# ai.net
KiCad netlist of a schematic drawn in Altium Designer
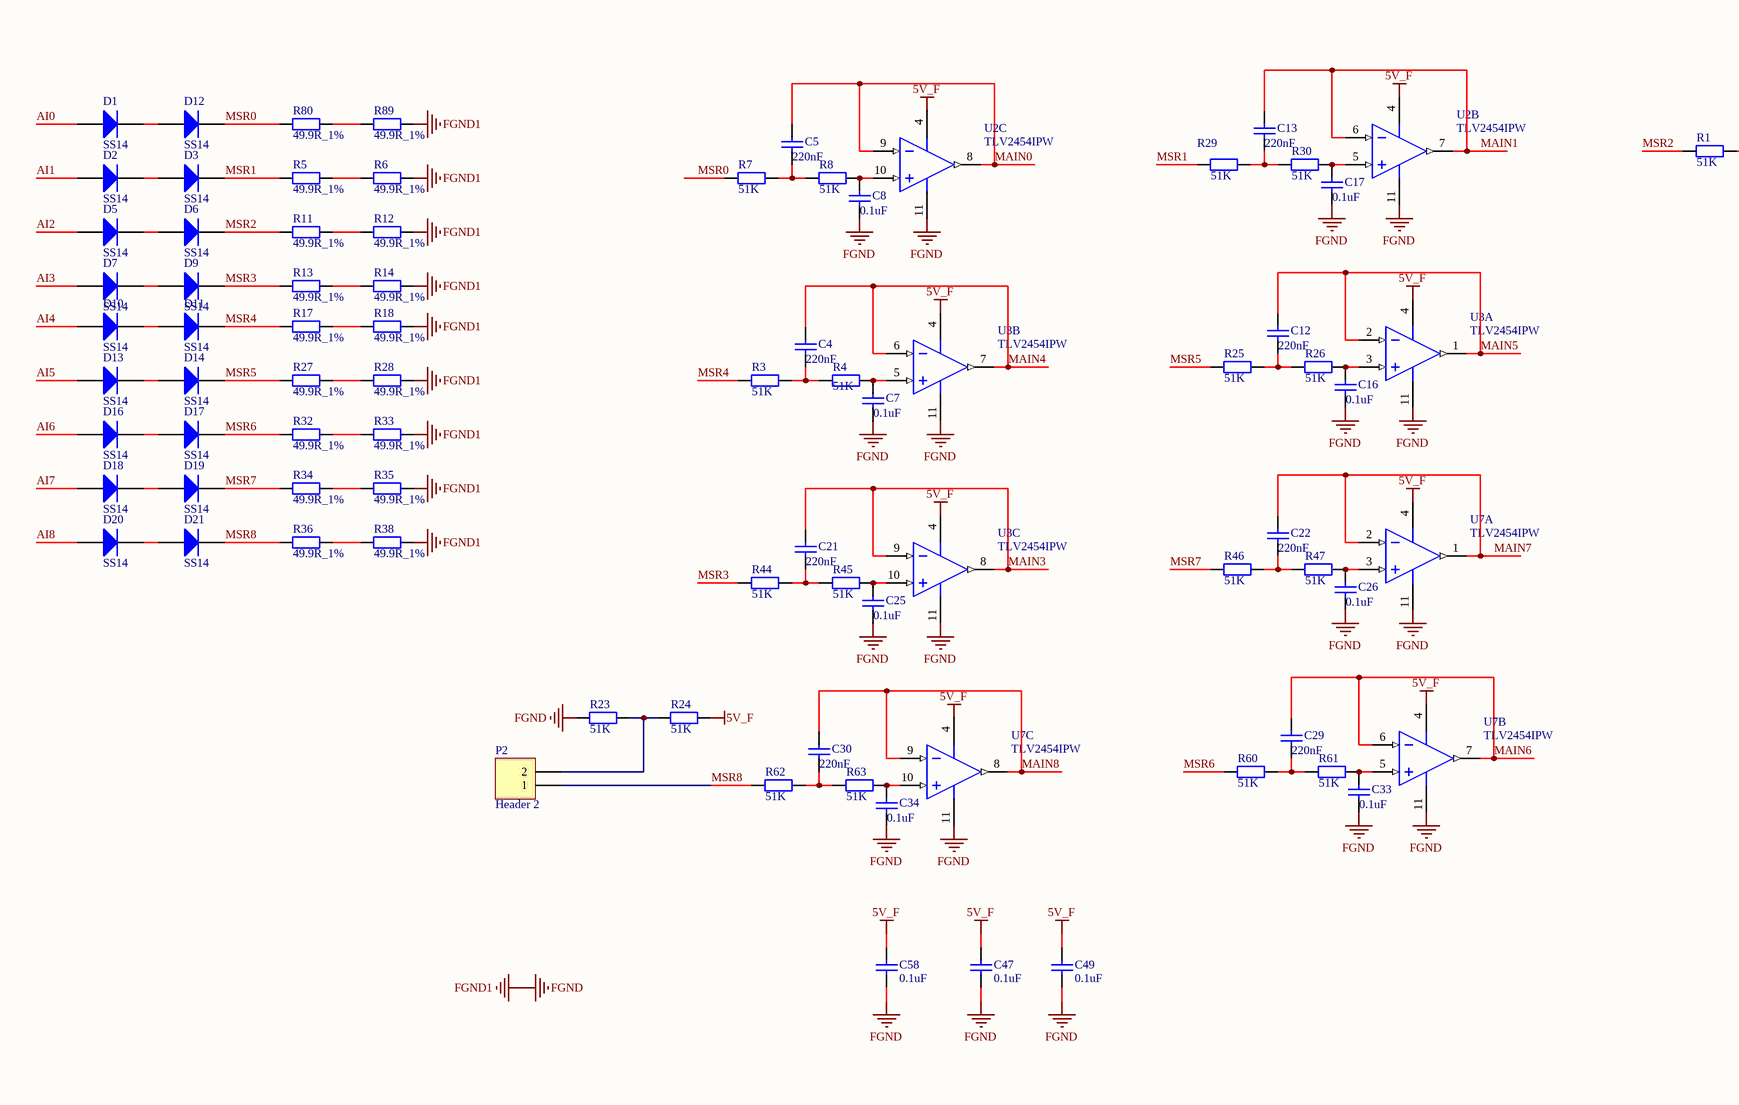
[diagram p0: ai.SchDoc, top left]
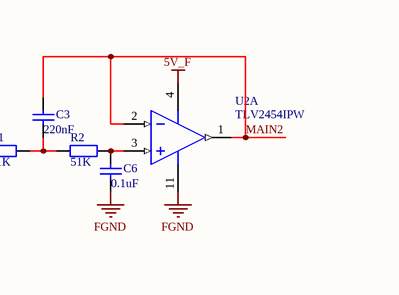
[diagram p1: ai.SchDoc, top right]
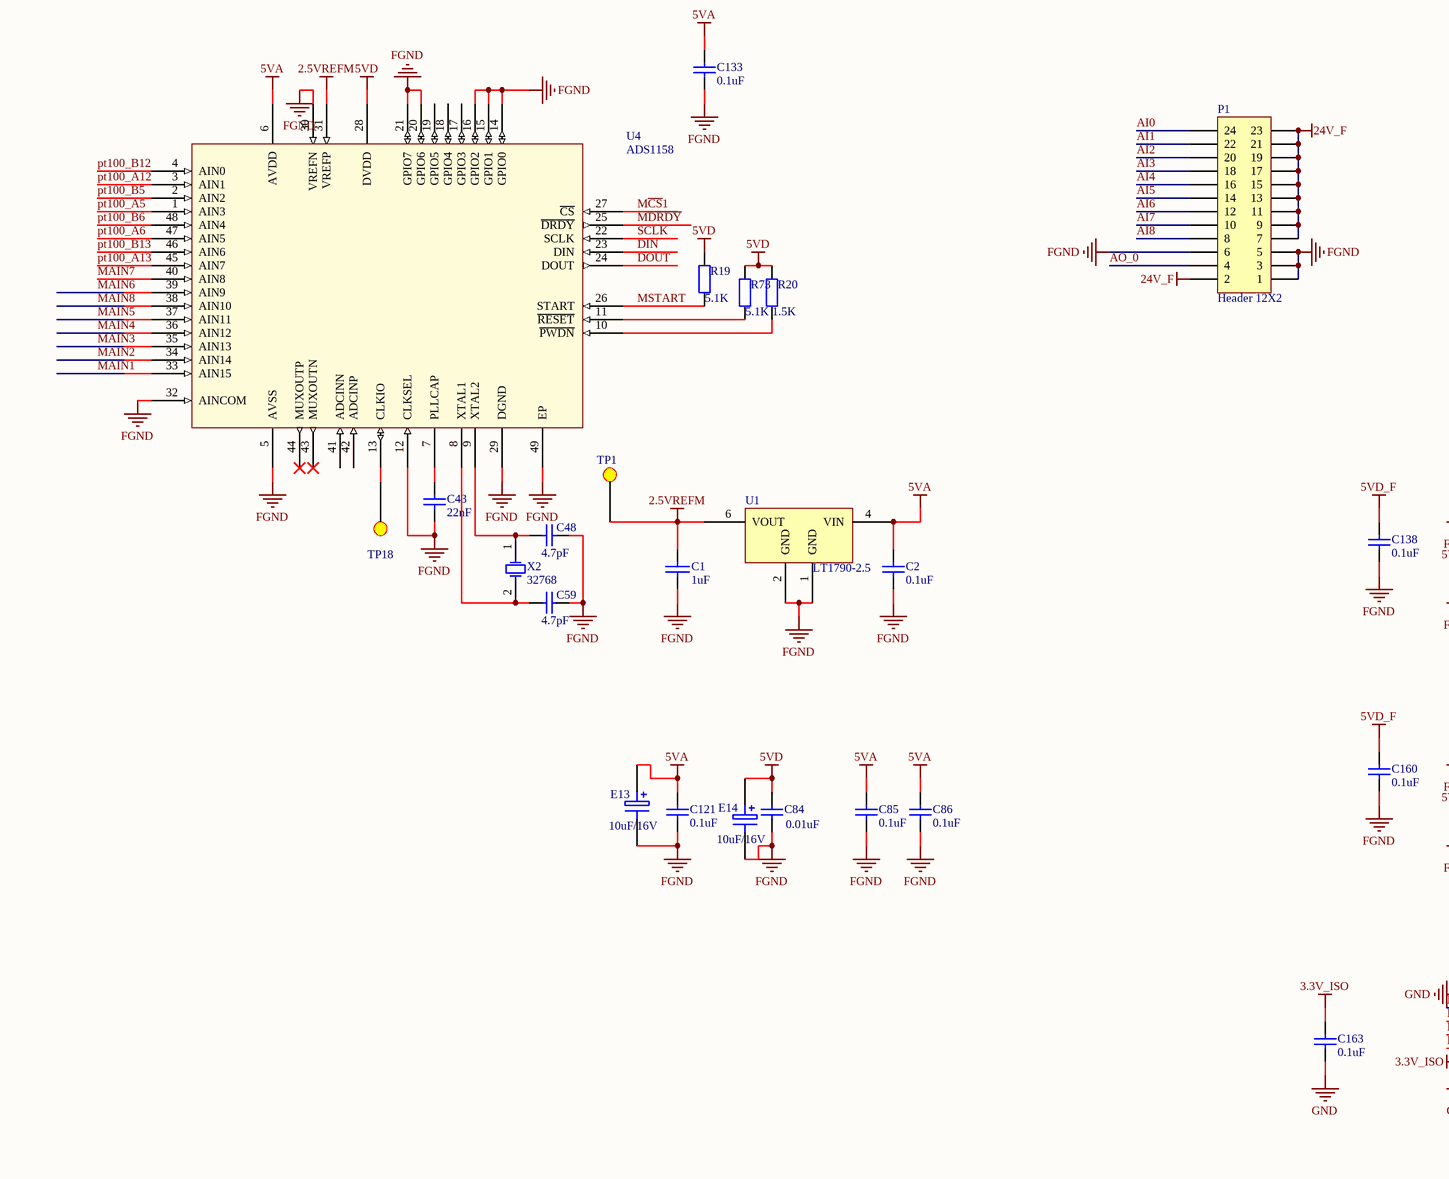
[diagram p2: ai.SchDoc, bottom left]
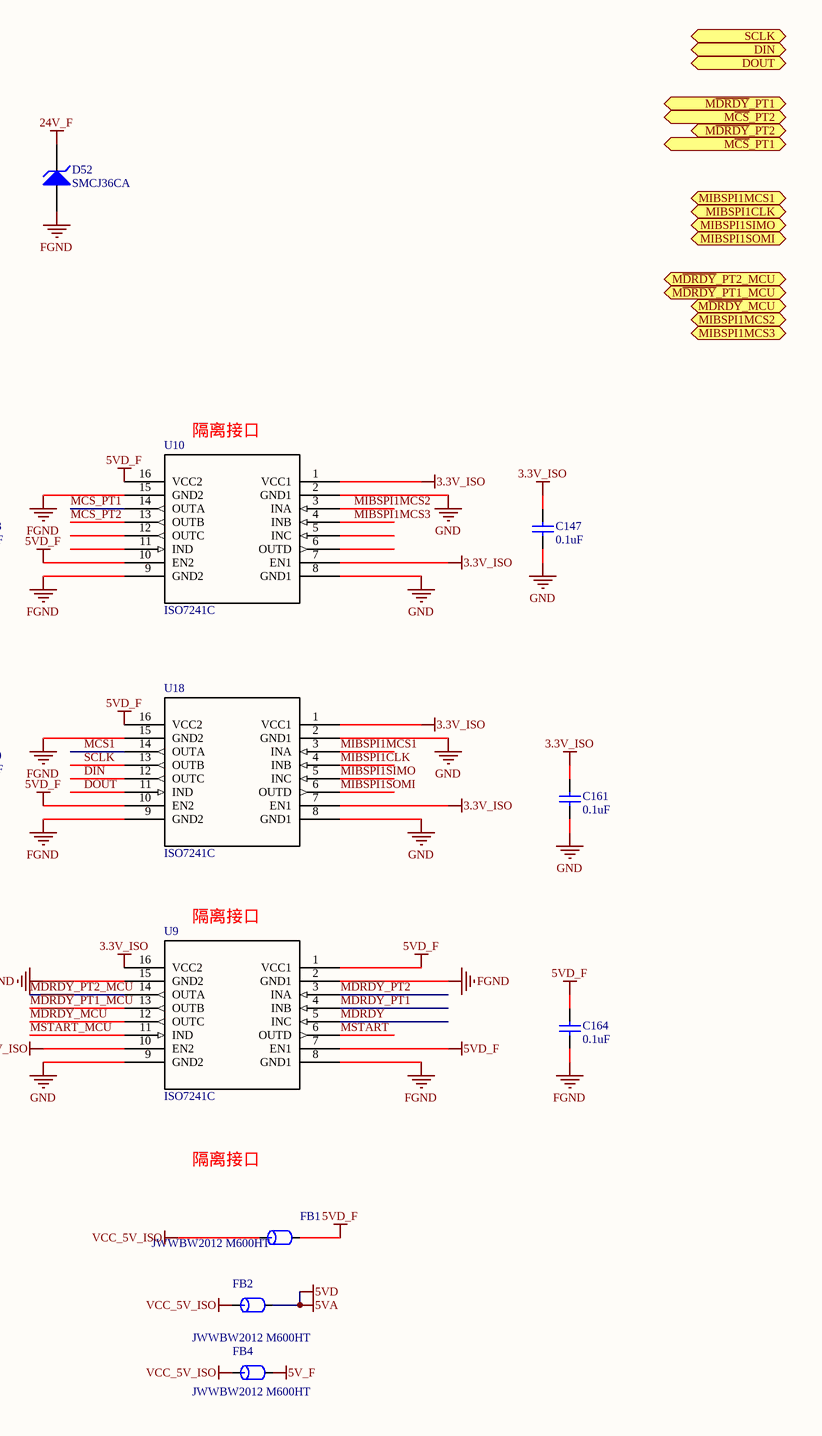
[diagram p3: ai.SchDoc, bottom right]

(export (version "E")
  (design (tool "Eeschema 10.0.6"))
  (components
    (comp (ref "C1")
      (value "1uF")
      (footprint "0603C")
      (description "Capacitor")
      (libsource (lib "*") (part "CAP"))
    )
    (comp (ref "C2")
      (value "0.1uF")
      (footprint "0603C")
      (description "Capacitor")
      (libsource (lib "Miscellaneous Devices") (part "Cap"))
    )
    (comp (ref "C3")
      (value "220nF")
      (footprint "0805C")
      (description "Capacitor")
      (libsource (lib "Miscellaneous Devices") (part "Cap"))
    )
    (comp (ref "C4")
      (value "220nF")
      (footprint "0805C")
      (description "Capacitor")
      (libsource (lib "Miscellaneous Devices") (part "Cap"))
    )
    (comp (ref "C5")
      (value "220nF")
      (footprint "0805C")
      (description "Capacitor")
      (libsource (lib "Miscellaneous Devices") (part "Cap"))
    )
    (comp (ref "C6")
      (value "0.1uF")
      (footprint "0603C")
      (description "Capacitor")
      (libsource (lib "Miscellaneous Devices") (part "Cap"))
    )
    (comp (ref "C7")
      (value "0.1uF")
      (footprint "0603C")
      (description "Capacitor")
      (libsource (lib "Miscellaneous Devices") (part "Cap"))
    )
    (comp (ref "C8")
      (value "0.1uF")
      (footprint "0603C")
      (description "Capacitor")
      (libsource (lib "Miscellaneous Devices") (part "Cap"))
    )
    (comp (ref "C12")
      (value "220nF")
      (footprint "0805C")
      (description "Capacitor")
      (libsource (lib "Miscellaneous Devices") (part "Cap"))
    )
    (comp (ref "C13")
      (value "220nF")
      (footprint "0805C")
      (description "Capacitor")
      (libsource (lib "Miscellaneous Devices") (part "Cap"))
    )
    (comp (ref "C16")
      (value "0.1uF")
      (footprint "0603C")
      (description "Capacitor")
      (libsource (lib "Miscellaneous Devices") (part "Cap"))
    )
    (comp (ref "C17")
      (value "0.1uF")
      (footprint "0603C")
      (description "Capacitor")
      (libsource (lib "Miscellaneous Devices") (part "Cap"))
    )
    (comp (ref "C21")
      (value "220nF")
      (footprint "0805C")
      (description "Capacitor")
      (libsource (lib "Miscellaneous Devices") (part "Cap"))
    )
    (comp (ref "C22")
      (value "220nF")
      (footprint "0805C")
      (description "Capacitor")
      (libsource (lib "Miscellaneous Devices") (part "Cap"))
    )
    (comp (ref "C25")
      (value "0.1uF")
      (footprint "0603C")
      (description "Capacitor")
      (libsource (lib "Miscellaneous Devices") (part "Cap"))
    )
    (comp (ref "C26")
      (value "0.1uF")
      (footprint "0603C")
      (description "Capacitor")
      (libsource (lib "Miscellaneous Devices") (part "Cap"))
    )
    (comp (ref "C29")
      (value "220nF")
      (footprint "0805C")
      (description "Capacitor")
      (libsource (lib "Miscellaneous Devices") (part "Cap"))
    )
    (comp (ref "C30")
      (value "220nF")
      (footprint "0805C")
      (description "Capacitor")
      (libsource (lib "Miscellaneous Devices") (part "Cap"))
    )
    (comp (ref "C33")
      (value "0.1uF")
      (footprint "0603C")
      (description "Capacitor")
      (libsource (lib "Miscellaneous Devices") (part "Cap"))
    )
    (comp (ref "C34")
      (value "0.1uF")
      (footprint "0603C")
      (description "Capacitor")
      (libsource (lib "Miscellaneous Devices") (part "Cap"))
    )
    (comp (ref "C43")
      (value "22nF")
      (footprint "0805C")
      (description "Capacitor")
      (libsource (lib "Miscellaneous Devices") (part "Cap"))
    )
    (comp (ref "C47")
      (value "0.1uF")
      (footprint "0603C")
      (description "Capacitor")
      (libsource (lib "Miscellaneous Devices") (part "Cap"))
    )
    (comp (ref "C48")
      (value "4.7pF")
      (footprint "0603C")
      (description "Capacitor")
      (libsource (lib "Miscellaneous Devices") (part "Cap"))
    )
    (comp (ref "C49")
      (value "0.1uF")
      (footprint "0603C")
      (description "Capacitor")
      (libsource (lib "Miscellaneous Devices") (part "Cap"))
    )
    (comp (ref "C58")
      (value "0.1uF")
      (footprint "0603C")
      (description "Capacitor")
      (libsource (lib "Miscellaneous Devices") (part "Cap"))
    )
    (comp (ref "C59")
      (value "4.7pF")
      (footprint "0603C")
      (description "Capacitor")
      (libsource (lib "Miscellaneous Devices") (part "Cap"))
    )
    (comp (ref "C84")
      (value "0.01uF")
      (footprint "0603C")
      (description "Capacitor")
      (libsource (lib "Miscellaneous Devices") (part "Cap"))
    )
    (comp (ref "C85")
      (value "0.1uF")
      (footprint "0603C")
      (description "Capacitor")
      (libsource (lib "Miscellaneous Devices") (part "Cap"))
    )
    (comp (ref "C86")
      (value "0.1uF")
      (footprint "0603C")
      (description "Capacitor")
      (libsource (lib "Miscellaneous Devices") (part "Cap"))
    )
    (comp (ref "C121")
      (value "0.1uF")
      (footprint "0603C")
      (description "Capacitor")
      (libsource (lib "Miscellaneous Devices") (part "Cap"))
    )
    (comp (ref "C133")
      (value "0.1uF")
      (footprint "0603C")
      (description "Capacitor")
      (libsource (lib "Miscellaneous Devices") (part "Cap"))
    )
    (comp (ref "C138")
      (value "0.1uF")
      (footprint "0603C")
      (description "Capacitor")
      (libsource (lib "Miscellaneous Devices") (part "Cap"))
    )
    (comp (ref "C147")
      (value "0.1uF")
      (footprint "0603C")
      (description "Capacitor")
      (libsource (lib "Miscellaneous Devices") (part "Cap"))
    )
    (comp (ref "C160")
      (value "0.1uF")
      (footprint "0603C")
      (description "Capacitor")
      (libsource (lib "Miscellaneous Devices") (part "Cap"))
    )
    (comp (ref "C161")
      (value "0.1uF")
      (footprint "0603C")
      (description "Capacitor")
      (libsource (lib "Miscellaneous Devices") (part "Cap"))
    )
    (comp (ref "C163")
      (value "0.1uF")
      (footprint "0603C")
      (description "Capacitor")
      (libsource (lib "Miscellaneous Devices") (part "Cap"))
    )
    (comp (ref "C164")
      (value "0.1uF")
      (footprint "0603C")
      (description "Capacitor")
      (libsource (lib "Miscellaneous Devices") (part "Cap"))
    )
    (comp (ref "D1")
      (value "SS14")
      (footprint "DO-214AC")
      (description "Default Diode")
      (libsource (lib "Miscellaneous Devices") (part "Diode"))
    )
    (comp (ref "D2")
      (value "SS14")
      (footprint "DO-214AC")
      (description "Default Diode")
      (libsource (lib "Miscellaneous Devices") (part "Diode"))
    )
    (comp (ref "D3")
      (value "SS14")
      (footprint "DO-214AC")
      (description "Default Diode")
      (libsource (lib "Miscellaneous Devices") (part "Diode"))
    )
    (comp (ref "D5")
      (value "SS14")
      (footprint "DO-214AC")
      (description "Default Diode")
      (libsource (lib "Miscellaneous Devices") (part "Diode"))
    )
    (comp (ref "D6")
      (value "SS14")
      (footprint "DO-214AC")
      (description "Default Diode")
      (libsource (lib "Miscellaneous Devices") (part "Diode"))
    )
    (comp (ref "D7")
      (value "SS14")
      (footprint "DO-214AC")
      (description "Default Diode")
      (libsource (lib "Miscellaneous Devices") (part "Diode"))
    )
    (comp (ref "D9")
      (value "SS14")
      (footprint "DO-214AC")
      (description "Default Diode")
      (libsource (lib "Miscellaneous Devices") (part "Diode"))
    )
    (comp (ref "D10")
      (value "SS14")
      (footprint "DO-214AC")
      (description "Default Diode")
      (libsource (lib "Miscellaneous Devices") (part "Diode"))
    )
    (comp (ref "D11")
      (value "SS14")
      (footprint "DO-214AC")
      (description "Default Diode")
      (libsource (lib "Miscellaneous Devices") (part "Diode"))
    )
    (comp (ref "D12")
      (value "SS14")
      (footprint "DO-214AC")
      (description "Default Diode")
      (libsource (lib "Miscellaneous Devices") (part "Diode"))
    )
    (comp (ref "D13")
      (value "SS14")
      (footprint "DO-214AC")
      (description "Default Diode")
      (libsource (lib "Miscellaneous Devices") (part "Diode"))
    )
    (comp (ref "D14")
      (value "SS14")
      (footprint "DO-214AC")
      (description "Default Diode")
      (libsource (lib "Miscellaneous Devices") (part "Diode"))
    )
    (comp (ref "D16")
      (value "SS14")
      (footprint "DO-214AC")
      (description "Default Diode")
      (libsource (lib "Miscellaneous Devices") (part "Diode"))
    )
    (comp (ref "D17")
      (value "SS14")
      (footprint "DO-214AC")
      (description "Default Diode")
      (libsource (lib "Miscellaneous Devices") (part "Diode"))
    )
    (comp (ref "D18")
      (value "SS14")
      (footprint "DO-214AC")
      (description "Default Diode")
      (libsource (lib "Miscellaneous Devices") (part "Diode"))
    )
    (comp (ref "D19")
      (value "SS14")
      (footprint "DO-214AC")
      (description "Default Diode")
      (libsource (lib "Miscellaneous Devices") (part "Diode"))
    )
    (comp (ref "D20")
      (value "SS14")
      (footprint "DO-214AC")
      (description "Default Diode")
      (libsource (lib "Miscellaneous Devices") (part "Diode"))
    )
    (comp (ref "D21")
      (value "SS14")
      (footprint "DO-214AC")
      (description "Default Diode")
      (libsource (lib "Miscellaneous Devices") (part "Diode"))
    )
    (comp (ref "D52")
      (value "SMCJ36CA")
      (footprint "SMC")
      (description "SMBJ36CA")
      (libsource (lib "Miscellaneous Devices") (part "D Zener"))
    )
    (comp (ref "E13")
      (value "10uF/16V")
      (footprint "C3528")
      (description "Electrolytic Capacitor")
      (libsource (lib "*") (part "ELECTRO1"))
    )
    (comp (ref "E14")
      (value "10uF/16V")
      (footprint "C3528")
      (description "Electrolytic Capacitor")
      (libsource (lib "*") (part "ELECTRO1"))
    )
    (comp (ref "FB1")
      (value "JWWBW2012 M600HT")
      (footprint "0805R")
      (libsource (lib "Schlib_20110825") (part "FB"))
    )
    (comp (ref "FB2")
      (value "JWWBW2012 M600HT")
      (footprint "0805R")
      (libsource (lib "Schlib_20110825") (part "FB"))
    )
    (comp (ref "FB4")
      (value "JWWBW2012 M600HT")
      (footprint "0805R")
      (libsource (lib "Schlib_20110825") (part "FB"))
    )
    (comp (ref "P1")
      (value "Header 12X2")
      (footprint "XH2.54_2x12")
      (description "Header, 12-Pin, Dual row")
      (libsource (lib "Miscellaneous Connectors") (part "Header 12X2"))
    )
    (comp (ref "P2")
      (value "Header 2")
      (footprint "HDR1X2")
      (description "Header, 2-Pin")
      (libsource (lib "Miscellaneous Connectors") (part "Header 2"))
    )
    (comp (ref "R1") (value "51K") (footprint "0603R") (libsource (lib "MQlibrary") (part "Res0805M")))
    (comp (ref "R2") (value "51K") (footprint "0603R") (libsource (lib "MQlibrary") (part "Res0805M")))
    (comp (ref "R3") (value "51K") (footprint "0603R") (libsource (lib "MQlibrary") (part "Res0805M")))
    (comp (ref "R4") (value "51K") (footprint "0603R") (libsource (lib "MQlibrary") (part "Res0805M")))
    (comp (ref "R5") (value "49.9R_1%") (footprint "0805R") (libsource (lib "MQlibrary") (part "Res0805M")))
    (comp (ref "R6") (value "49.9R_1%") (footprint "0805R") (libsource (lib "MQlibrary") (part "Res0805M")))
    (comp (ref "R7") (value "51K") (footprint "0603R") (libsource (lib "MQlibrary") (part "Res0805M")))
    (comp (ref "R8") (value "51K") (footprint "0603R") (libsource (lib "MQlibrary") (part "Res0805M")))
    (comp (ref "R11") (value "49.9R_1%") (footprint "0805R") (libsource (lib "MQlibrary") (part "Res0805M")))
    (comp (ref "R12") (value "49.9R_1%") (footprint "0805R") (libsource (lib "MQlibrary") (part "Res0805M")))
    (comp (ref "R13") (value "49.9R_1%") (footprint "0805R") (libsource (lib "MQlibrary") (part "Res0805M")))
    (comp (ref "R14") (value "49.9R_1%") (footprint "0805R") (libsource (lib "MQlibrary") (part "Res0805M")))
    (comp (ref "R17") (value "49.9R_1%") (footprint "0805R") (libsource (lib "MQlibrary") (part "Res0805M")))
    (comp (ref "R18") (value "49.9R_1%") (footprint "0805R") (libsource (lib "MQlibrary") (part "Res0805M")))
    (comp (ref "R19") (value "5.1K") (footprint "0603R") (libsource (lib "") (part "Res0805M_1")))
    (comp (ref "R20") (value "1.5K") (footprint "0603R") (libsource (lib "") (part "Res0805M_1")))
    (comp (ref "R23") (value "51K") (footprint "0603R") (libsource (lib "") (part "Res0805M_2")))
    (comp (ref "R24") (value "51K") (footprint "0603R") (libsource (lib "") (part "Res0805M_2")))
    (comp (ref "R25") (value "51K") (footprint "0603R") (libsource (lib "MQlibrary") (part "Res0805M")))
    (comp (ref "R26") (value "51K") (footprint "0603R") (libsource (lib "MQlibrary") (part "Res0805M")))
    (comp (ref "R27") (value "49.9R_1%") (footprint "0805R") (libsource (lib "MQlibrary") (part "Res0805M")))
    (comp (ref "R28") (value "49.9R_1%") (footprint "0805R") (libsource (lib "MQlibrary") (part "Res0805M")))
    (comp (ref "R29") (value "51K") (footprint "0603R") (libsource (lib "MQlibrary") (part "Res0805M")))
    (comp (ref "R30") (value "51K") (footprint "0603R") (libsource (lib "MQlibrary") (part "Res0805M")))
    (comp (ref "R32") (value "49.9R_1%") (footprint "0805R") (libsource (lib "MQlibrary") (part "Res0805M")))
    (comp (ref "R33") (value "49.9R_1%") (footprint "0805R") (libsource (lib "MQlibrary") (part "Res0805M")))
    (comp (ref "R34") (value "49.9R_1%") (footprint "0805R") (libsource (lib "MQlibrary") (part "Res0805M")))
    (comp (ref "R35") (value "49.9R_1%") (footprint "0805R") (libsource (lib "MQlibrary") (part "Res0805M")))
    (comp (ref "R36") (value "49.9R_1%") (footprint "0805R") (libsource (lib "MQlibrary") (part "Res0805M")))
    (comp (ref "R38") (value "49.9R_1%") (footprint "0805R") (libsource (lib "MQlibrary") (part "Res0805M")))
    (comp (ref "R44") (value "51K") (footprint "0603R") (libsource (lib "MQlibrary") (part "Res0805M")))
    (comp (ref "R45") (value "51K") (footprint "0603R") (libsource (lib "MQlibrary") (part "Res0805M")))
    (comp (ref "R46") (value "51K") (footprint "0603R") (libsource (lib "MQlibrary") (part "Res0805M")))
    (comp (ref "R47") (value "51K") (footprint "0603R") (libsource (lib "MQlibrary") (part "Res0805M")))
    (comp (ref "R60") (value "51K") (footprint "0603R") (libsource (lib "MQlibrary") (part "Res0805M")))
    (comp (ref "R61") (value "51K") (footprint "0603R") (libsource (lib "MQlibrary") (part "Res0805M")))
    (comp (ref "R62") (value "51K") (footprint "0603R") (libsource (lib "MQlibrary") (part "Res0805M")))
    (comp (ref "R63") (value "51K") (footprint "0603R") (libsource (lib "MQlibrary") (part "Res0805M")))
    (comp (ref "R73") (value "5.1K") (footprint "0603R") (libsource (lib "") (part "Res0805M_1")))
    (comp (ref "R80") (value "49.9R_1%") (footprint "0805R") (libsource (lib "MQlibrary") (part "Res0805M")))
    (comp (ref "R89") (value "49.9R_1%") (footprint "0805R") (libsource (lib "MQlibrary") (part "Res0805M")))
    (comp (ref "TP1")
      (value "TEST_POINT")
      (footprint "TPD")
      (libsource (lib "基带芯片OEM板_V1P0_张猛_20120921") (part "TEST_POINT"))
    )
    (comp (ref "TP18")
      (value "TEST_POINT")
      (footprint "TPD")
      (libsource (lib "基带芯片OEM板_V1P0_张猛_20120921") (part "TEST_POINT"))
    )
    (comp (ref "U1")
      (value "LT1790-2.5")
      (footprint "SOT23-6")
      (description "2.5V Micropower SOT-23  Low Dropout Reference")
      (libsource (lib "Schlib") (part "LT1790-2.5"))
    )
    (comp (ref "U2")
      (value "TLV2454IPW")
      (footprint "TSSOP14")
      (description "Quad High-speed, Ultra Low-power, Single-Supply TTL comparator")
      (libsource (lib "Maxim Analog Comparator") (part "MAX908EPD"))
    )
    (comp (ref "U3")
      (value "TLV2454IPW")
      (footprint "TSSOP14")
      (description "Quad High-speed, Ultra Low-power, Single-Supply TTL comparator")
      (libsource (lib "Maxim Analog Comparator") (part "MAX908EPD"))
    )
    (comp (ref "U4")
      (value "ADS1158")
      (footprint "S-PVFQN-N48")
      (description "16-Channel, 16-Bit Analog-to-Digital Converter")
      (libsource (lib "Schlib") (part "ADS1158"))
    )
    (comp (ref "U7")
      (value "TLV2454IPW")
      (footprint "TSSOP14")
      (description "Quad High-speed, Ultra Low-power, Single-Supply TTL comparator")
      (libsource (lib "Maxim Analog Comparator") (part "MAX908EPD"))
    )
    (comp (ref "U9") (value "ISO7241C") (footprint "SOIC16") (libsource (lib "DI16") (part "ISO7241C")))
    (comp (ref "U10") (value "ISO7241C") (footprint "SOIC16") (libsource (lib "DI16") (part "ISO7241C")))
    (comp (ref "U18") (value "ISO7241C") (footprint "SOIC16") (libsource (lib "DI16") (part "ISO7241C")))
    (comp (ref "X2")
      (value "32768")
      (footprint "A")
      (description "Crystal Oscillator")
      (libsource (lib "Miscellaneous Devices") (part "XTAL"))
    )
  )
  (nets
    (net (code "1") (name "/AI0") (class "Default")
      (node (ref "D1") (pin "1") (pinfunction "A_1") (pintype "passive"))
      (node (ref "P1") (pin "24") (pinfunction "24_24") (pintype "passive"))
    )
    (net (code "2") (name "/AI1") (class "Default")
      (node (ref "D2") (pin "1") (pinfunction "A_1") (pintype "passive"))
      (node (ref "P1") (pin "22") (pinfunction "22_22") (pintype "passive"))
    )
    (net (code "3") (name "/AI2") (class "Default")
      (node (ref "D5") (pin "1") (pinfunction "A_1") (pintype "passive"))
      (node (ref "P1") (pin "20") (pinfunction "20_20") (pintype "passive"))
    )
    (net (code "4") (name "/AI3") (class "Default")
      (node (ref "D7") (pin "1") (pinfunction "A_1") (pintype "passive"))
      (node (ref "P1") (pin "18") (pinfunction "18_18") (pintype "passive"))
    )
    (net (code "5") (name "/AI4") (class "Default")
      (node (ref "D10") (pin "1") (pinfunction "A_1") (pintype "passive"))
      (node (ref "P1") (pin "16") (pinfunction "16_16") (pintype "passive"))
    )
    (net (code "6") (name "/AI5") (class "Default")
      (node (ref "D13") (pin "1") (pinfunction "A_1") (pintype "passive"))
      (node (ref "P1") (pin "14") (pinfunction "14_14") (pintype "passive"))
    )
    (net (code "7") (name "/AI6") (class "Default")
      (node (ref "D16") (pin "1") (pinfunction "A_1") (pintype "passive"))
      (node (ref "P1") (pin "12") (pinfunction "12_12") (pintype "passive"))
    )
    (net (code "8") (name "/AI7") (class "Default")
      (node (ref "D18") (pin "1") (pinfunction "A_1") (pintype "passive"))
      (node (ref "P1") (pin "10") (pinfunction "10_10") (pintype "passive"))
    )
    (net (code "9") (name "/AI8") (class "Default")
      (node (ref "D20") (pin "1") (pinfunction "A_1") (pintype "passive"))
      (node (ref "P1") (pin "8") (pinfunction "8_8") (pintype "passive"))
    )
    (net (code "10") (name "/AO_0") (class "Default")
      (node (ref "P1") (pin "4") (pinfunction "4_4") (pintype "passive"))
    )
    (net (code "11") (name "/DIN") (class "Default")
      (node (ref "U18") (pin "12") (pinfunction "OUTC_12") (pintype "output"))
      (node (ref "U4") (pin "23") (pinfunction "DIN_23") (pintype "input"))
    )
    (net (code "12") (name "/DOUT") (class "Default")
      (node (ref "U18") (pin "11") (pinfunction "IND_11") (pintype "input"))
      (node (ref "U4") (pin "24") (pinfunction "DOUT_24") (pintype "output"))
    )
    (net (code "13") (name "/MAIN0") (class "Default")
      (node (ref "C5") (pin "2") (pinfunction "2_2") (pintype "passive"))
      (node (ref "U2") (pin "8") (pinfunction "OUT_8") (pintype "output"))
      (node (ref "U2") (pin "9") (pinfunction "IN-_9") (pintype "input"))
    )
    (net (code "14") (name "/MAIN1") (class "Default")
      (node (ref "C13") (pin "2") (pinfunction "2_2") (pintype "passive"))
      (node (ref "U2") (pin "6") (pinfunction "IN-_6") (pintype "input"))
      (node (ref "U2") (pin "7") (pinfunction "OUT_7") (pintype "output"))
      (node (ref "U4") (pin "33") (pinfunction "AIN15_33") (pintype "input"))
    )
    (net (code "15") (name "/MAIN2") (class "Default")
      (node (ref "C3") (pin "2") (pinfunction "2_2") (pintype "passive"))
      (node (ref "U2") (pin "1") (pinfunction "OUT_1") (pintype "output"))
      (node (ref "U2") (pin "2") (pinfunction "IN-_2") (pintype "input"))
      (node (ref "U4") (pin "34") (pinfunction "AIN14_34") (pintype "input"))
    )
    (net (code "16") (name "/MAIN3") (class "Default")
      (node (ref "C21") (pin "2") (pinfunction "2_2") (pintype "passive"))
      (node (ref "U3") (pin "8") (pinfunction "OUT_8") (pintype "output"))
      (node (ref "U3") (pin "9") (pinfunction "IN-_9") (pintype "input"))
      (node (ref "U4") (pin "35") (pinfunction "AIN13_35") (pintype "input"))
    )
    (net (code "17") (name "/MAIN4") (class "Default")
      (node (ref "C4") (pin "2") (pinfunction "2_2") (pintype "passive"))
      (node (ref "U3") (pin "6") (pinfunction "IN-_6") (pintype "input"))
      (node (ref "U3") (pin "7") (pinfunction "OUT_7") (pintype "output"))
      (node (ref "U4") (pin "36") (pinfunction "AIN12_36") (pintype "input"))
    )
    (net (code "18") (name "/MAIN5") (class "Default")
      (node (ref "C12") (pin "2") (pinfunction "2_2") (pintype "passive"))
      (node (ref "U3") (pin "1") (pinfunction "OUT_1") (pintype "output"))
      (node (ref "U3") (pin "2") (pinfunction "IN-_2") (pintype "input"))
      (node (ref "U4") (pin "37") (pinfunction "AIN11_37") (pintype "input"))
    )
    (net (code "19") (name "/MAIN6") (class "Default")
      (node (ref "C29") (pin "2") (pinfunction "2_2") (pintype "passive"))
      (node (ref "U4") (pin "39") (pinfunction "AIN9_39") (pintype "input"))
      (node (ref "U7") (pin "6") (pinfunction "IN-_6") (pintype "input"))
      (node (ref "U7") (pin "7") (pinfunction "OUT_7") (pintype "output"))
    )
    (net (code "20") (name "/MAIN7") (class "Default")
      (node (ref "C22") (pin "2") (pinfunction "2_2") (pintype "passive"))
      (node (ref "U4") (pin "40") (pinfunction "AIN8_40") (pintype "input"))
      (node (ref "U7") (pin "1") (pinfunction "OUT_1") (pintype "output"))
      (node (ref "U7") (pin "2") (pinfunction "IN-_2") (pintype "input"))
    )
    (net (code "21") (name "/MAIN8") (class "Default")
      (node (ref "C30") (pin "2") (pinfunction "2_2") (pintype "passive"))
      (node (ref "U4") (pin "38") (pinfunction "AIN10_38") (pintype "input"))
      (node (ref "U7") (pin "8") (pinfunction "OUT_8") (pintype "output"))
      (node (ref "U7") (pin "9") (pinfunction "IN-_9") (pintype "input"))
    )
    (net (code "22") (name "/MIBSPI1CLK") (class "Default")
      (node (ref "U18") (pin "4") (pinfunction "INB_4") (pintype "input"))
    )
    (net (code "23") (name "/MIBSPI1MCS1") (class "Default")
      (node (ref "U18") (pin "3") (pinfunction "INA_3") (pintype "input"))
    )
    (net (code "24") (name "/MIBSPI1MCS2") (class "Default")
      (node (ref "U10") (pin "3") (pinfunction "INA_3") (pintype "input"))
    )
    (net (code "25") (name "/MIBSPI1MCS3") (class "Default")
      (node (ref "U10") (pin "4") (pinfunction "INB_4") (pintype "input"))
    )
    (net (code "26") (name "/MIBSPI1SIMO") (class "Default")
      (node (ref "U18") (pin "5") (pinfunction "INC_5") (pintype "input"))
    )
    (net (code "27") (name "/MIBSPI1SOMI") (class "Default")
      (node (ref "U18") (pin "6") (pinfunction "OUTD_6") (pintype "output"))
    )
    (net (code "28") (name "/MSR0") (class "Default")
      (node (ref "D12") (pin "2") (pinfunction "K_2") (pintype "passive"))
      (node (ref "R7") (pin "2") (pinfunction "2_2") (pintype "passive"))
      (node (ref "R80") (pin "2") (pinfunction "2_2") (pintype "passive"))
    )
    (net (code "29") (name "/MSR1") (class "Default")
      (node (ref "D3") (pin "2") (pinfunction "K_2") (pintype "passive"))
      (node (ref "R29") (pin "2") (pinfunction "2_2") (pintype "passive"))
      (node (ref "R5") (pin "2") (pinfunction "2_2") (pintype "passive"))
    )
    (net (code "30") (name "/MSR2") (class "Default")
      (node (ref "D6") (pin "2") (pinfunction "K_2") (pintype "passive"))
      (node (ref "R1") (pin "2") (pinfunction "2_2") (pintype "passive"))
      (node (ref "R11") (pin "2") (pinfunction "2_2") (pintype "passive"))
    )
    (net (code "31") (name "/MSR3") (class "Default")
      (node (ref "D9") (pin "2") (pinfunction "K_2") (pintype "passive"))
      (node (ref "R13") (pin "2") (pinfunction "2_2") (pintype "passive"))
      (node (ref "R44") (pin "2") (pinfunction "2_2") (pintype "passive"))
    )
    (net (code "32") (name "/MSR4") (class "Default")
      (node (ref "D11") (pin "2") (pinfunction "K_2") (pintype "passive"))
      (node (ref "R17") (pin "2") (pinfunction "2_2") (pintype "passive"))
      (node (ref "R3") (pin "2") (pinfunction "2_2") (pintype "passive"))
    )
    (net (code "33") (name "/MSR5") (class "Default")
      (node (ref "D14") (pin "2") (pinfunction "K_2") (pintype "passive"))
      (node (ref "R25") (pin "2") (pinfunction "2_2") (pintype "passive"))
      (node (ref "R27") (pin "2") (pinfunction "2_2") (pintype "passive"))
    )
    (net (code "34") (name "/MSR6") (class "Default")
      (node (ref "D17") (pin "2") (pinfunction "K_2") (pintype "passive"))
      (node (ref "R32") (pin "2") (pinfunction "2_2") (pintype "passive"))
      (node (ref "R60") (pin "2") (pinfunction "2_2") (pintype "passive"))
    )
    (net (code "35") (name "/MSR7") (class "Default")
      (node (ref "D19") (pin "2") (pinfunction "K_2") (pintype "passive"))
      (node (ref "R34") (pin "2") (pinfunction "2_2") (pintype "passive"))
      (node (ref "R46") (pin "2") (pinfunction "2_2") (pintype "passive"))
    )
    (net (code "36") (name "/MSR8") (class "Default")
      (node (ref "D21") (pin "2") (pinfunction "K_2") (pintype "passive"))
      (node (ref "P2") (pin "1") (pinfunction "1_1") (pintype "passive"))
      (node (ref "R36") (pin "2") (pinfunction "2_2") (pintype "passive"))
      (node (ref "R62") (pin "2") (pinfunction "2_2") (pintype "passive"))
    )
    (net (code "37") (name "/MSTART") (class "Default")
      (node (ref "R19") (pin "2") (pinfunction "2_2") (pintype "passive"))
      (node (ref "U4") (pin "26") (pinfunction "START_26") (pintype "input"))
      (node (ref "U9") (pin "6") (pinfunction "OUTD_6") (pintype "output"))
    )
    (net (code "38") (name "/MSTART_MCU") (class "Default")
      (node (ref "U9") (pin "11") (pinfunction "IND_11") (pintype "input"))
    )
    (net (code "39") (name "/M~{CS}1") (class "Default")
      (node (ref "U18") (pin "14") (pinfunction "OUTA_14") (pintype "output"))
      (node (ref "U4") (pin "27") (pinfunction "~{CS}_27") (pintype "input"))
    )
    (net (code "40") (name "/M~{CS}_PT1") (class "Default")
      (node (ref "U10") (pin "14") (pinfunction "OUTA_14") (pintype "output"))
    )
    (net (code "41") (name "/M~{CS}_PT2") (class "Default")
      (node (ref "U10") (pin "13") (pinfunction "OUTB_13") (pintype "output"))
    )
    (net (code "42") (name "/M~{DRDY}") (class "Default")
      (node (ref "U4") (pin "25") (pinfunction "~{DRDY}_25") (pintype "output"))
      (node (ref "U9") (pin "5") (pinfunction "INC_5") (pintype "input"))
    )
    (net (code "43") (name "/M~{DRDY}_MCU") (class "Default")
      (node (ref "U9") (pin "12") (pinfunction "OUTC_12") (pintype "output"))
    )
    (net (code "44") (name "/M~{DRDY}_PT1") (class "Default")
      (node (ref "U9") (pin "4") (pinfunction "INB_4") (pintype "input"))
    )
    (net (code "45") (name "/M~{DRDY}_PT1_MCU") (class "Default")
      (node (ref "U9") (pin "13") (pinfunction "OUTB_13") (pintype "output"))
    )
    (net (code "46") (name "/M~{DRDY}_PT2") (class "Default")
      (node (ref "U9") (pin "3") (pinfunction "INA_3") (pintype "input"))
    )
    (net (code "47") (name "/M~{DRDY}_PT2_MCU") (class "Default")
      (node (ref "U9") (pin "14") (pinfunction "OUTA_14") (pintype "output"))
    )
    (net (code "48") (name "/SCLK") (class "Default")
      (node (ref "U18") (pin "13") (pinfunction "OUTB_13") (pintype "output"))
      (node (ref "U4") (pin "22") (pinfunction "SCLK_22") (pintype "input"))
    )
    (net (code "49") (name "/pt100_A5") (class "Default")
      (node (ref "U4") (pin "1") (pinfunction "AIN3_1") (pintype "input"))
    )
    (net (code "50") (name "/pt100_A6") (class "Default")
      (node (ref "U4") (pin "47") (pinfunction "AIN5_47") (pintype "input"))
    )
    (net (code "51") (name "/pt100_A12") (class "Default")
      (node (ref "U4") (pin "3") (pinfunction "AIN1_3") (pintype "input"))
    )
    (net (code "52") (name "/pt100_A13") (class "Default")
      (node (ref "U4") (pin "45") (pinfunction "AIN7_45") (pintype "input"))
    )
    (net (code "53") (name "/pt100_B5") (class "Default")
      (node (ref "U4") (pin "2") (pinfunction "AIN2_2") (pintype "input"))
    )
    (net (code "54") (name "/pt100_B6") (class "Default")
      (node (ref "U4") (pin "48") (pinfunction "AIN4_48") (pintype "input"))
    )
    (net (code "55") (name "/pt100_B12") (class "Default")
      (node (ref "U4") (pin "4") (pinfunction "AIN0_4") (pintype "input"))
    )
    (net (code "56") (name "/pt100_B13") (class "Default")
      (node (ref "U4") (pin "46") (pinfunction "AIN6_46") (pintype "input"))
    )
    (net (code "57") (name "2.5VREFM") (class "Default")
      (node (ref "C1") (pin "1") (pinfunction "1_1") (pintype "passive"))
      (node (ref "TP1") (pin "1") (pinfunction "1_1") (pintype "passive"))
      (node (ref "U1") (pin "6") (pinfunction "VOUT_6") (pintype "power_in"))
      (node (ref "U4") (pin "31") (pinfunction "VREFP_31") (pintype "input"))
    )
    (net (code "58") (name "3.3V_ISO") (class "Default")
      (node (ref "C147") (pin "2") (pinfunction "2_2") (pintype "passive"))
      (node (ref "C161") (pin "2") (pinfunction "2_2") (pintype "passive"))
      (node (ref "C163") (pin "2") (pinfunction "2_2") (pintype "passive"))
      (node (ref "U10") (pin "1") (pinfunction "VCC1_1") (pintype "power_in"))
      (node (ref "U10") (pin "7") (pinfunction "EN1_7") (pintype "passive"))
      (node (ref "U18") (pin "1") (pinfunction "VCC1_1") (pintype "power_in"))
      (node (ref "U18") (pin "7") (pinfunction "EN1_7") (pintype "passive"))
      (node (ref "U9") (pin "10") (pinfunction "EN2_10") (pintype "passive"))
      (node (ref "U9") (pin "16") (pinfunction "VCC2_16") (pintype "power_in"))
    )
    (net (code "59") (name "5VA") (class "Default")
      (node (ref "C121") (pin "2") (pinfunction "2_2") (pintype "passive"))
      (node (ref "C133") (pin "2") (pinfunction "2_2") (pintype "passive"))
      (node (ref "C2") (pin "2") (pinfunction "2_2") (pintype "passive"))
      (node (ref "C84") (pin "2") (pinfunction "2_2") (pintype "passive"))
      (node (ref "C85") (pin "2") (pinfunction "2_2") (pintype "passive"))
      (node (ref "C86") (pin "2") (pinfunction "2_2") (pintype "passive"))
      (node (ref "E13") (pin "1") (pinfunction "1_1") (pintype "passive"))
      (node (ref "E14") (pin "1") (pinfunction "1_1") (pintype "passive"))
      (node (ref "FB2") (pin "2") (pintype "passive"))
      (node (ref "R19") (pin "1") (pinfunction "1_1") (pintype "passive"))
      (node (ref "R20") (pin "1") (pinfunction "1_1") (pintype "passive"))
      (node (ref "R73") (pin "1") (pinfunction "1_1") (pintype "passive"))
      (node (ref "U1") (pin "4") (pinfunction "VIN_4") (pintype "power_in"))
      (node (ref "U4") (pin "28") (pinfunction "DVDD_28") (pintype "power_in"))
      (node (ref "U4") (pin "6") (pinfunction "AVDD_6") (pintype "passive"))
    )
    (net (code "60") (name "5VD_F") (class "Default")
      (node (ref "C138") (pin "2") (pinfunction "2_2") (pintype "passive"))
      (node (ref "C160") (pin "2") (pinfunction "2_2") (pintype "passive"))
      (node (ref "C164") (pin "2") (pinfunction "2_2") (pintype "passive"))
      (node (ref "FB1") (pin "2") (pintype "passive"))
      (node (ref "U10") (pin "10") (pinfunction "EN2_10") (pintype "passive"))
      (node (ref "U10") (pin "16") (pinfunction "VCC2_16") (pintype "power_in"))
      (node (ref "U18") (pin "10") (pinfunction "EN2_10") (pintype "passive"))
      (node (ref "U18") (pin "16") (pinfunction "VCC2_16") (pintype "power_in"))
      (node (ref "U9") (pin "1") (pinfunction "VCC1_1") (pintype "power_in"))
      (node (ref "U9") (pin "7") (pinfunction "EN1_7") (pintype "passive"))
    )
    (net (code "61") (name "5V_F") (class "Default")
      (node (ref "C47") (pin "2") (pinfunction "2_2") (pintype "passive"))
      (node (ref "C49") (pin "2") (pinfunction "2_2") (pintype "passive"))
      (node (ref "C58") (pin "2") (pinfunction "2_2") (pintype "passive"))
      (node (ref "FB4") (pin "2") (pintype "passive"))
      (node (ref "R24") (pin "2") (pinfunction "2_2") (pintype "passive"))
      (node (ref "U2") (pin "4") (pinfunction "V+_4") (pintype "power_in"))
      (node (ref "U3") (pin "4") (pinfunction "V+_4") (pintype "power_in"))
      (node (ref "U7") (pin "4") (pinfunction "V+_4") (pintype "power_in"))
    )
    (net (code "62") (name "24V_F") (class "Default")
      (node (ref "D52") (pin "2") (pinfunction "K_2") (pintype "passive"))
      (node (ref "P1") (pin "11") (pinfunction "11_11") (pintype "passive"))
      (node (ref "P1") (pin "13") (pinfunction "13_13") (pintype "passive"))
      (node (ref "P1") (pin "15") (pinfunction "15_15") (pintype "passive"))
      (node (ref "P1") (pin "17") (pinfunction "17_17") (pintype "passive"))
      (node (ref "P1") (pin "19") (pinfunction "19_19") (pintype "passive"))
      (node (ref "P1") (pin "2") (pinfunction "2_2") (pintype "passive"))
      (node (ref "P1") (pin "21") (pinfunction "21_21") (pintype "passive"))
      (node (ref "P1") (pin "23") (pinfunction "23_23") (pintype "passive"))
      (node (ref "P1") (pin "7") (pinfunction "7_7") (pintype "passive"))
      (node (ref "P1") (pin "9") (pinfunction "9_9") (pintype "passive"))
    )
    (net (code "63") (name "FGND") (class "Default")
      (node (ref "C1") (pin "2") (pinfunction "2_2") (pintype "passive"))
      (node (ref "C121") (pin "1") (pinfunction "1_1") (pintype "passive"))
      (node (ref "C133") (pin "1") (pinfunction "1_1") (pintype "passive"))
      (node (ref "C138") (pin "1") (pinfunction "1_1") (pintype "passive"))
      (node (ref "C16") (pin "1") (pinfunction "1_1") (pintype "passive"))
      (node (ref "C160") (pin "1") (pinfunction "1_1") (pintype "passive"))
      (node (ref "C164") (pin "1") (pinfunction "1_1") (pintype "passive"))
      (node (ref "C17") (pin "1") (pinfunction "1_1") (pintype "passive"))
      (node (ref "C2") (pin "1") (pinfunction "1_1") (pintype "passive"))
      (node (ref "C25") (pin "1") (pinfunction "1_1") (pintype "passive"))
      (node (ref "C26") (pin "1") (pinfunction "1_1") (pintype "passive"))
      (node (ref "C33") (pin "1") (pinfunction "1_1") (pintype "passive"))
      (node (ref "C34") (pin "1") (pinfunction "1_1") (pintype "passive"))
      (node (ref "C43") (pin "2") (pinfunction "2_2") (pintype "passive"))
      (node (ref "C47") (pin "1") (pinfunction "1_1") (pintype "passive"))
      (node (ref "C48") (pin "2") (pinfunction "2_2") (pintype "passive"))
      (node (ref "C49") (pin "1") (pinfunction "1_1") (pintype "passive"))
      (node (ref "C58") (pin "1") (pinfunction "1_1") (pintype "passive"))
      (node (ref "C59") (pin "2") (pinfunction "2_2") (pintype "passive"))
      (node (ref "C6") (pin "1") (pinfunction "1_1") (pintype "passive"))
      (node (ref "C7") (pin "1") (pinfunction "1_1") (pintype "passive"))
      (node (ref "C8") (pin "1") (pinfunction "1_1") (pintype "passive"))
      (node (ref "C84") (pin "1") (pinfunction "1_1") (pintype "passive"))
      (node (ref "C85") (pin "1") (pinfunction "1_1") (pintype "passive"))
      (node (ref "C86") (pin "1") (pinfunction "1_1") (pintype "passive"))
      (node (ref "D52") (pin "1") (pinfunction "A_1") (pintype "passive"))
      (node (ref "E13") (pin "2") (pinfunction "2_2") (pintype "passive"))
      (node (ref "E14") (pin "2") (pinfunction "2_2") (pintype "passive"))
      (node (ref "P1") (pin "1") (pinfunction "1_1") (pintype "passive"))
      (node (ref "P1") (pin "3") (pinfunction "3_3") (pintype "passive"))
      (node (ref "P1") (pin "5") (pinfunction "5_5") (pintype "passive"))
      (node (ref "P1") (pin "6") (pinfunction "6_6") (pintype "passive"))
      (node (ref "R12") (pin "1") (pinfunction "1_1") (pintype "passive"))
      (node (ref "R14") (pin "1") (pinfunction "1_1") (pintype "passive"))
      (node (ref "R18") (pin "1") (pinfunction "1_1") (pintype "passive"))
      (node (ref "R23") (pin "1") (pinfunction "1_1") (pintype "passive"))
      (node (ref "R28") (pin "1") (pinfunction "1_1") (pintype "passive"))
      (node (ref "R33") (pin "1") (pinfunction "1_1") (pintype "passive"))
      (node (ref "R35") (pin "1") (pinfunction "1_1") (pintype "passive"))
      (node (ref "R38") (pin "1") (pinfunction "1_1") (pintype "passive"))
      (node (ref "R6") (pin "1") (pinfunction "1_1") (pintype "passive"))
      (node (ref "R89") (pin "1") (pinfunction "1_1") (pintype "passive"))
      (node (ref "U1") (pin "1") (pinfunction "GND_1") (pintype "power_in"))
      (node (ref "U1") (pin "2") (pinfunction "GND_2") (pintype "power_in"))
      (node (ref "U10") (pin "15") (pinfunction "GND2_15") (pintype "power_in"))
      (node (ref "U10") (pin "9") (pinfunction "GND2_9") (pintype "power_in"))
      (node (ref "U18") (pin "15") (pinfunction "GND2_15") (pintype "power_in"))
      (node (ref "U18") (pin "9") (pinfunction "GND2_9") (pintype "power_in"))
      (node (ref "U2") (pin "11") (pinfunction "GND_11") (pintype "power_in"))
      (node (ref "U3") (pin "11") (pinfunction "GND_11") (pintype "power_in"))
      (node (ref "U4") (pin "12") (pinfunction "CLKSEL_12") (pintype "input"))
      (node (ref "U4") (pin "14") (pinfunction "GPIO0_14") (pintype "bidirectional"))
      (node (ref "U4") (pin "15") (pinfunction "GPIO1_15") (pintype "bidirectional"))
      (node (ref "U4") (pin "16") (pinfunction "GPIO2_16") (pintype "bidirectional"))
      (node (ref "U4") (pin "20") (pinfunction "GPIO6_20") (pintype "bidirectional"))
      (node (ref "U4") (pin "21") (pinfunction "GPIO7_21") (pintype "bidirectional"))
      (node (ref "U4") (pin "29") (pinfunction "DGND_29") (pintype "power_in"))
      (node (ref "U4") (pin "30") (pinfunction "VREFN_30") (pintype "input"))
      (node (ref "U4") (pin "32") (pinfunction "AINCOM_32") (pintype "input"))
      (node (ref "U4") (pin "49") (pinfunction "EP_49") (pintype "passive"))
      (node (ref "U4") (pin "5") (pinfunction "AVSS_5") (pintype "power_in"))
      (node (ref "U7") (pin "11") (pinfunction "GND_11") (pintype "power_in"))
      (node (ref "U9") (pin "2") (pinfunction "GND1_2") (pintype "power_in"))
      (node (ref "U9") (pin "8") (pinfunction "GND1_8") (pintype "power_in"))
    )
    (net (code "64") (name "GND") (class "Default")
      (node (ref "C147") (pin "1") (pinfunction "1_1") (pintype "passive"))
      (node (ref "C161") (pin "1") (pinfunction "1_1") (pintype "passive"))
      (node (ref "C163") (pin "1") (pinfunction "1_1") (pintype "passive"))
      (node (ref "U10") (pin "2") (pinfunction "GND1_2") (pintype "power_in"))
      (node (ref "U10") (pin "8") (pinfunction "GND1_8") (pintype "power_in"))
      (node (ref "U18") (pin "2") (pinfunction "GND1_2") (pintype "power_in"))
      (node (ref "U18") (pin "8") (pinfunction "GND1_8") (pintype "power_in"))
      (node (ref "U9") (pin "15") (pinfunction "GND2_15") (pintype "power_in"))
      (node (ref "U9") (pin "9") (pinfunction "GND2_9") (pintype "power_in"))
    )
    (net (code "65") (name "Net-(C3-Pad1)") (class "Default")
      (node (ref "C3") (pin "1") (pinfunction "1_1") (pintype "passive"))
      (node (ref "R1") (pin "1") (pinfunction "1_1") (pintype "passive"))
      (node (ref "R2") (pin "2") (pinfunction "2_2") (pintype "passive"))
    )
    (net (code "66") (name "Net-(C4-Pad1)") (class "Default")
      (node (ref "C4") (pin "1") (pinfunction "1_1") (pintype "passive"))
      (node (ref "R3") (pin "1") (pinfunction "1_1") (pintype "passive"))
      (node (ref "R4") (pin "2") (pinfunction "2_2") (pintype "passive"))
    )
    (net (code "67") (name "Net-(C5-Pad1)") (class "Default")
      (node (ref "C5") (pin "1") (pinfunction "1_1") (pintype "passive"))
      (node (ref "R7") (pin "1") (pinfunction "1_1") (pintype "passive"))
      (node (ref "R8") (pin "2") (pinfunction "2_2") (pintype "passive"))
    )
    (net (code "68") (name "Net-(C12-Pad1)") (class "Default")
      (node (ref "C12") (pin "1") (pinfunction "1_1") (pintype "passive"))
      (node (ref "R25") (pin "1") (pinfunction "1_1") (pintype "passive"))
      (node (ref "R26") (pin "2") (pinfunction "2_2") (pintype "passive"))
    )
    (net (code "69") (name "Net-(C13-Pad1)") (class "Default")
      (node (ref "C13") (pin "1") (pinfunction "1_1") (pintype "passive"))
      (node (ref "R29") (pin "1") (pinfunction "1_1") (pintype "passive"))
      (node (ref "R30") (pin "2") (pinfunction "2_2") (pintype "passive"))
    )
    (net (code "70") (name "Net-(C21-Pad1)") (class "Default")
      (node (ref "C21") (pin "1") (pinfunction "1_1") (pintype "passive"))
      (node (ref "R44") (pin "1") (pinfunction "1_1") (pintype "passive"))
      (node (ref "R45") (pin "2") (pinfunction "2_2") (pintype "passive"))
    )
    (net (code "71") (name "Net-(C22-Pad1)") (class "Default")
      (node (ref "C22") (pin "1") (pinfunction "1_1") (pintype "passive"))
      (node (ref "R46") (pin "1") (pinfunction "1_1") (pintype "passive"))
      (node (ref "R47") (pin "2") (pinfunction "2_2") (pintype "passive"))
    )
    (net (code "72") (name "Net-(C29-Pad1)") (class "Default")
      (node (ref "C29") (pin "1") (pinfunction "1_1") (pintype "passive"))
      (node (ref "R60") (pin "1") (pinfunction "1_1") (pintype "passive"))
      (node (ref "R61") (pin "2") (pinfunction "2_2") (pintype "passive"))
    )
    (net (code "73") (name "Net-(C30-Pad1)") (class "Default")
      (node (ref "C30") (pin "1") (pinfunction "1_1") (pintype "passive"))
      (node (ref "R62") (pin "1") (pinfunction "1_1") (pintype "passive"))
      (node (ref "R63") (pin "2") (pinfunction "2_2") (pintype "passive"))
    )
    (net (code "74") (name "Net-(D1-K)") (class "Default")
      (node (ref "D1") (pin "2") (pinfunction "K_2") (pintype "passive"))
      (node (ref "D12") (pin "1") (pinfunction "A_1") (pintype "passive"))
    )
    (net (code "75") (name "Net-(D2-K)") (class "Default")
      (node (ref "D2") (pin "2") (pinfunction "K_2") (pintype "passive"))
      (node (ref "D3") (pin "1") (pinfunction "A_1") (pintype "passive"))
    )
    (net (code "76") (name "Net-(D5-K)") (class "Default")
      (node (ref "D5") (pin "2") (pinfunction "K_2") (pintype "passive"))
      (node (ref "D6") (pin "1") (pinfunction "A_1") (pintype "passive"))
    )
    (net (code "77") (name "Net-(D7-K)") (class "Default")
      (node (ref "D7") (pin "2") (pinfunction "K_2") (pintype "passive"))
      (node (ref "D9") (pin "1") (pinfunction "A_1") (pintype "passive"))
    )
    (net (code "78") (name "Net-(D10-K)") (class "Default")
      (node (ref "D10") (pin "2") (pinfunction "K_2") (pintype "passive"))
      (node (ref "D11") (pin "1") (pinfunction "A_1") (pintype "passive"))
    )
    (net (code "79") (name "Net-(D13-K)") (class "Default")
      (node (ref "D13") (pin "2") (pinfunction "K_2") (pintype "passive"))
      (node (ref "D14") (pin "1") (pinfunction "A_1") (pintype "passive"))
    )
    (net (code "80") (name "Net-(D16-K)") (class "Default")
      (node (ref "D16") (pin "2") (pinfunction "K_2") (pintype "passive"))
      (node (ref "D17") (pin "1") (pinfunction "A_1") (pintype "passive"))
    )
    (net (code "81") (name "Net-(D18-K)") (class "Default")
      (node (ref "D18") (pin "2") (pinfunction "K_2") (pintype "passive"))
      (node (ref "D19") (pin "1") (pinfunction "A_1") (pintype "passive"))
    )
    (net (code "82") (name "Net-(D20-K)") (class "Default")
      (node (ref "D20") (pin "2") (pinfunction "K_2") (pintype "passive"))
      (node (ref "D21") (pin "1") (pinfunction "A_1") (pintype "passive"))
    )
    (net (code "83") (name "Net-(P2-Pad2)") (class "Default")
      (node (ref "P2") (pin "2") (pinfunction "2_2") (pintype "passive"))
      (node (ref "R23") (pin "2") (pinfunction "2_2") (pintype "passive"))
      (node (ref "R24") (pin "1") (pinfunction "1_1") (pintype "passive"))
    )
    (net (code "84") (name "Net-(R5-Pad1)") (class "Default")
      (node (ref "R5") (pin "1") (pinfunction "1_1") (pintype "passive"))
      (node (ref "R6") (pin "2") (pinfunction "2_2") (pintype "passive"))
    )
    (net (code "85") (name "Net-(R11-Pad1)") (class "Default")
      (node (ref "R11") (pin "1") (pinfunction "1_1") (pintype "passive"))
      (node (ref "R12") (pin "2") (pinfunction "2_2") (pintype "passive"))
    )
    (net (code "86") (name "Net-(R13-Pad1)") (class "Default")
      (node (ref "R13") (pin "1") (pinfunction "1_1") (pintype "passive"))
      (node (ref "R14") (pin "2") (pinfunction "2_2") (pintype "passive"))
    )
    (net (code "87") (name "Net-(R17-Pad1)") (class "Default")
      (node (ref "R17") (pin "1") (pinfunction "1_1") (pintype "passive"))
      (node (ref "R18") (pin "2") (pinfunction "2_2") (pintype "passive"))
    )
    (net (code "88") (name "Net-(R27-Pad1)") (class "Default")
      (node (ref "R27") (pin "1") (pinfunction "1_1") (pintype "passive"))
      (node (ref "R28") (pin "2") (pinfunction "2_2") (pintype "passive"))
    )
    (net (code "89") (name "Net-(R32-Pad1)") (class "Default")
      (node (ref "R32") (pin "1") (pinfunction "1_1") (pintype "passive"))
      (node (ref "R33") (pin "2") (pinfunction "2_2") (pintype "passive"))
    )
    (net (code "90") (name "Net-(R34-Pad1)") (class "Default")
      (node (ref "R34") (pin "1") (pinfunction "1_1") (pintype "passive"))
      (node (ref "R35") (pin "2") (pinfunction "2_2") (pintype "passive"))
    )
    (net (code "91") (name "Net-(R36-Pad1)") (class "Default")
      (node (ref "R36") (pin "1") (pinfunction "1_1") (pintype "passive"))
      (node (ref "R38") (pin "2") (pinfunction "2_2") (pintype "passive"))
    )
    (net (code "92") (name "Net-(R80-Pad1)") (class "Default")
      (node (ref "R80") (pin "1") (pinfunction "1_1") (pintype "passive"))
      (node (ref "R89") (pin "2") (pinfunction "2_2") (pintype "passive"))
    )
    (net (code "93") (name "Net-(U2A-IN+)") (class "Default")
      (node (ref "C6") (pin "2") (pinfunction "2_2") (pintype "passive"))
      (node (ref "R2") (pin "1") (pinfunction "1_1") (pintype "passive"))
      (node (ref "U2") (pin "3") (pinfunction "IN+_3") (pintype "input"))
    )
    (net (code "94") (name "Net-(U2B-IN+)") (class "Default")
      (node (ref "C17") (pin "2") (pinfunction "2_2") (pintype "passive"))
      (node (ref "R30") (pin "1") (pinfunction "1_1") (pintype "passive"))
      (node (ref "U2") (pin "5") (pinfunction "IN+_5") (pintype "input"))
    )
    (net (code "95") (name "Net-(U2C-IN+)") (class "Default")
      (node (ref "C8") (pin "2") (pinfunction "2_2") (pintype "passive"))
      (node (ref "R8") (pin "1") (pinfunction "1_1") (pintype "passive"))
      (node (ref "U2") (pin "10") (pinfunction "IN+_10") (pintype "input"))
    )
    (net (code "96") (name "Net-(U3A-IN+)") (class "Default")
      (node (ref "C16") (pin "2") (pinfunction "2_2") (pintype "passive"))
      (node (ref "R26") (pin "1") (pinfunction "1_1") (pintype "passive"))
      (node (ref "U3") (pin "3") (pinfunction "IN+_3") (pintype "input"))
    )
    (net (code "97") (name "Net-(U3B-IN+)") (class "Default")
      (node (ref "C7") (pin "2") (pinfunction "2_2") (pintype "passive"))
      (node (ref "R4") (pin "1") (pinfunction "1_1") (pintype "passive"))
      (node (ref "U3") (pin "5") (pinfunction "IN+_5") (pintype "input"))
    )
    (net (code "98") (name "Net-(U3C-IN+)") (class "Default")
      (node (ref "C25") (pin "2") (pinfunction "2_2") (pintype "passive"))
      (node (ref "R45") (pin "1") (pinfunction "1_1") (pintype "passive"))
      (node (ref "U3") (pin "10") (pinfunction "IN+_10") (pintype "input"))
    )
    (net (code "99") (name "Net-(U4-CLKIO)") (class "Default")
      (node (ref "TP18") (pin "1") (pinfunction "1_1") (pintype "passive"))
      (node (ref "U4") (pin "13") (pinfunction "CLKIO_13") (pintype "bidirectional"))
    )
    (net (code "100") (name "Net-(U4-PLLCAP)") (class "Default")
      (node (ref "C43") (pin "1") (pinfunction "1_1") (pintype "passive"))
      (node (ref "U4") (pin "7") (pinfunction "PLLCAP_7") (pintype "power_in"))
    )
    (net (code "101") (name "Net-(U4-XTAL1)") (class "Default")
      (node (ref "C59") (pin "1") (pinfunction "1_1") (pintype "passive"))
      (node (ref "U4") (pin "8") (pinfunction "XTAL1_8") (pintype "passive"))
      (node (ref "X2") (pin "2") (pinfunction "OSC2_2") (pintype "passive"))
    )
    (net (code "102") (name "Net-(U4-XTAL2)") (class "Default")
      (node (ref "C48") (pin "1") (pinfunction "1_1") (pintype "passive"))
      (node (ref "U4") (pin "9") (pinfunction "XTAL2_9") (pintype "passive"))
      (node (ref "X2") (pin "1") (pinfunction "OSC1_1") (pintype "passive"))
    )
    (net (code "103") (name "Net-(U4-~{PWDN})") (class "Default")
      (node (ref "R20") (pin "2") (pinfunction "2_2") (pintype "passive"))
      (node (ref "U4") (pin "10") (pinfunction "~{PWDN}_10") (pintype "input"))
    )
    (net (code "104") (name "Net-(U4-~{RESET})") (class "Default")
      (node (ref "R73") (pin "2") (pinfunction "2_2") (pintype "passive"))
      (node (ref "U4") (pin "11") (pinfunction "~{RESET}_11") (pintype "input"))
    )
    (net (code "105") (name "Net-(U7A-IN+)") (class "Default")
      (node (ref "C26") (pin "2") (pinfunction "2_2") (pintype "passive"))
      (node (ref "R47") (pin "1") (pinfunction "1_1") (pintype "passive"))
      (node (ref "U7") (pin "3") (pinfunction "IN+_3") (pintype "input"))
    )
    (net (code "106") (name "Net-(U7B-IN+)") (class "Default")
      (node (ref "C33") (pin "2") (pinfunction "2_2") (pintype "passive"))
      (node (ref "R61") (pin "1") (pinfunction "1_1") (pintype "passive"))
      (node (ref "U7") (pin "5") (pinfunction "IN+_5") (pintype "input"))
    )
    (net (code "107") (name "Net-(U7C-IN+)") (class "Default")
      (node (ref "C34") (pin "2") (pinfunction "2_2") (pintype "passive"))
      (node (ref "R63") (pin "1") (pinfunction "1_1") (pintype "passive"))
      (node (ref "U7") (pin "10") (pinfunction "IN+_10") (pintype "input"))
    )
    (net (code "108") (name "VCC_5V_ISO") (class "Default")
      (node (ref "FB1") (pin "1") (pintype "passive"))
      (node (ref "FB2") (pin "1") (pintype "passive"))
      (node (ref "FB4") (pin "1") (pintype "passive"))
    )
    (net (code "109") (name "unconnected-(U1-DNC-Pad3)") (class "Default")
      (node (ref "U1") (pin "3") (pinfunction "DNC_3") (pintype "passive"))
    )
    (net (code "110") (name "unconnected-(U1-DNC-Pad5)") (class "Default")
      (node (ref "U1") (pin "5") (pinfunction "DNC_5") (pintype "passive"))
    )
    (net (code "111") (name "unconnected-(U4-ADCINN-Pad41)") (class "Default")
      (node (ref "U4") (pin "41") (pinfunction "ADCINN_41") (pintype "input"))
    )
    (net (code "112") (name "unconnected-(U4-ADCINP-Pad42)") (class "Default")
      (node (ref "U4") (pin "42") (pinfunction "ADCINP_42") (pintype "input"))
    )
    (net (code "113") (name "unconnected-(U4-GPIO3-Pad17)") (class "Default")
      (node (ref "U4") (pin "17") (pinfunction "GPIO3_17") (pintype "bidirectional"))
    )
    (net (code "114") (name "unconnected-(U4-GPIO4-Pad18)") (class "Default")
      (node (ref "U4") (pin "18") (pinfunction "GPIO4_18") (pintype "bidirectional"))
    )
    (net (code "115") (name "unconnected-(U4-GPIO5-Pad19)") (class "Default")
      (node (ref "U4") (pin "19") (pinfunction "GPIO5_19") (pintype "bidirectional"))
    )
    (net (code "116") (name "unconnected-(U4-MUXOUTN-Pad43)") (class "Default")
      (node (ref "U4") (pin "43") (pinfunction "MUXOUTN_43") (pintype "output+no_connect"))
    )
    (net (code "117") (name "unconnected-(U4-MUXOUTP-Pad44)") (class "Default")
      (node (ref "U4") (pin "44") (pinfunction "MUXOUTP_44") (pintype "output+no_connect"))
    )
    (net (code "118") (name "unconnected-(U10-INC-Pad5)") (class "Default")
      (node (ref "U10") (pin "5") (pinfunction "INC_5") (pintype "input"))
    )
    (net (code "119") (name "unconnected-(U10-IND-Pad11)") (class "Default")
      (node (ref "U10") (pin "11") (pinfunction "IND_11") (pintype "input"))
    )
    (net (code "120") (name "unconnected-(U10-OUTC-Pad12)") (class "Default")
      (node (ref "U10") (pin "12") (pinfunction "OUTC_12") (pintype "output"))
    )
    (net (code "121") (name "unconnected-(U10-OUTD-Pad6)") (class "Default")
      (node (ref "U10") (pin "6") (pinfunction "OUTD_6") (pintype "output"))
    )
  )
)
